# 2_WIZ750SR_Transceiver.net
KiCad netlist of a schematic drawn in Altium Designer
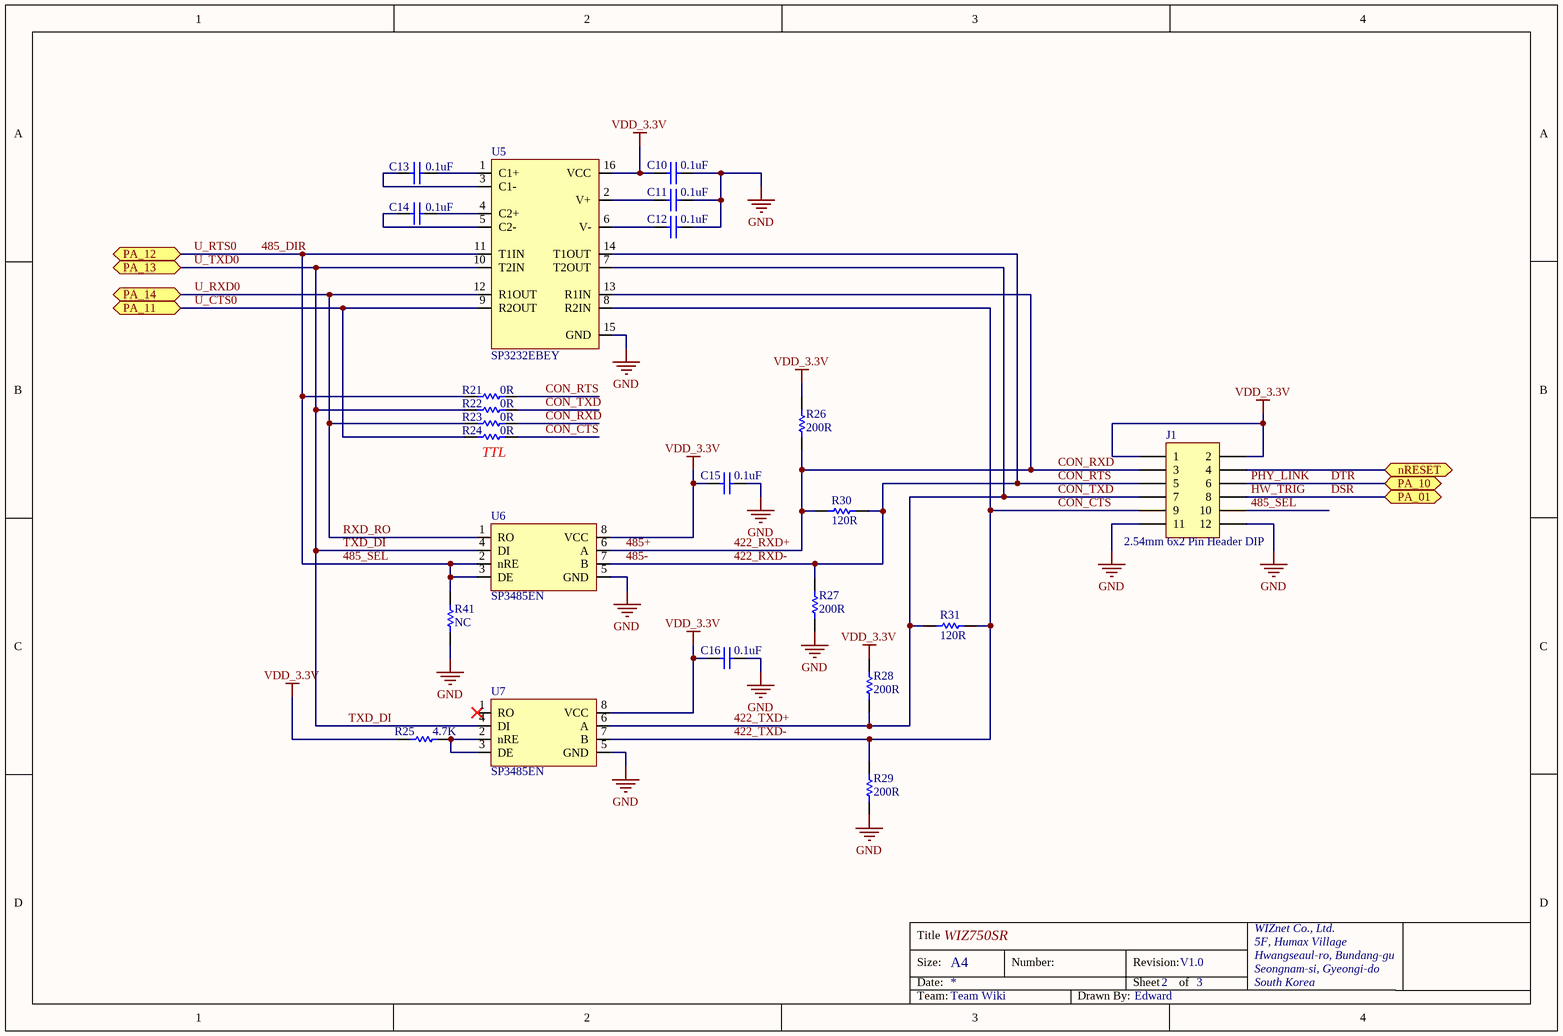
[diagram p0: 2.WIZ750SR_Transceiver.SchDoc]

(export (version "E")
  (design (tool "Eeschema 10.0.6"))
  (components
    (comp (ref "C10")
      (value "0.1uF")
      (footprint "CAP-0402")
      (description "Ceramic CAP 0402(1005)")
      (libsource (lib "Scott_lib") (part "CAP-0402"))
    )
    (comp (ref "C11")
      (value "0.1uF")
      (footprint "CAP-0402")
      (description "Ceramic CAP 0402(1005)")
      (libsource (lib "Scott_lib") (part "CAP-0402"))
    )
    (comp (ref "C12")
      (value "0.1uF")
      (footprint "CAP-0402")
      (description "Ceramic CAP 0402(1005)")
      (libsource (lib "Scott_lib") (part "CAP-0402"))
    )
    (comp (ref "C13")
      (value "0.1uF")
      (footprint "CAP-0402")
      (description "Ceramic CAP 0402(1005)")
      (libsource (lib "Scott_lib") (part "CAP-0402"))
    )
    (comp (ref "C14")
      (value "0.1uF")
      (footprint "CAP-0402")
      (description "Ceramic CAP 0402(1005)")
      (libsource (lib "Scott_lib") (part "CAP-0402"))
    )
    (comp (ref "C15")
      (value "0.1uF")
      (footprint "CAP-0402")
      (description "Ceramic CAP 0402(1005)")
      (libsource (lib "Scott_lib") (part "CAP-0402"))
    )
    (comp (ref "C16")
      (value "0.1uF")
      (footprint "CAP-0402")
      (description "Ceramic CAP 0402(1005)")
      (libsource (lib "Scott_lib") (part "CAP-0402"))
    )
    (comp (ref "J1")
      (value "2.54mm 6x2 Pin Header DIP")
      (footprint "IDC-2X6")
      (description "Header, 6-Pin, Dual row")
      (fields (field (name "PUBLISHER") "Altium Limited"))
      (libsource (lib "Miscellaneous Connectors") (part "Header 6X2"))
    )
    (comp (ref "R21")
      (value "0R")
      (footprint "RES-0402")
      (description "RES-0402")
      (libsource (lib "Scott_lib") (part "RES-0402"))
    )
    (comp (ref "R22")
      (value "0R")
      (footprint "RES-0402")
      (description "RES-0402")
      (libsource (lib "Scott_lib") (part "RES-0402"))
    )
    (comp (ref "R23")
      (value "0R")
      (footprint "RES-0402")
      (description "RES-0402")
      (libsource (lib "Scott_lib") (part "RES-0402"))
    )
    (comp (ref "R24")
      (value "0R")
      (footprint "RES-0402")
      (description "RES-0402")
      (libsource (lib "Scott_lib") (part "RES-0402"))
    )
    (comp (ref "R25")
      (value "4.7K")
      (footprint "RES-0402")
      (description "RES-0402")
      (libsource (lib "Scott_lib") (part "RES-0402"))
    )
    (comp (ref "R26")
      (value "200R")
      (footprint "RES-0402")
      (description "RES-0402")
      (libsource (lib "Scott_lib") (part "RES-0402"))
    )
    (comp (ref "R27")
      (value "200R")
      (footprint "RES-0402")
      (description "RES-0402")
      (libsource (lib "Scott_lib") (part "RES-0402"))
    )
    (comp (ref "R28")
      (value "200R")
      (footprint "RES-0402")
      (description "RES-0402")
      (libsource (lib "Scott_lib") (part "RES-0402"))
    )
    (comp (ref "R29")
      (value "200R")
      (footprint "RES-0402")
      (description "RES-0402")
      (libsource (lib "Scott_lib") (part "RES-0402"))
    )
    (comp (ref "R30")
      (value "120R")
      (footprint "RES-0402")
      (description "RES-0402")
      (libsource (lib "Scott_lib") (part "RES-0402"))
    )
    (comp (ref "R31")
      (value "120R")
      (footprint "RES-0402")
      (description "RES-0402")
      (libsource (lib "Scott_lib") (part "RES-0402"))
    )
    (comp (ref "R41")
      (value "NC")
      (footprint "RES-0402")
      (description "RES-0402")
      (libsource (lib "Scott_lib") (part "RES-0402"))
    )
    (comp (ref "U5")
      (value "SP3232EBEY")
      (footprint "TSSOP16(0.65/6.4)")
      (description "True +3.0V to +5.5V RS-232 Transceivers TSSOP16")
      (libsource (lib "Scott_lib") (part "SP3232EBEY"))
    )
    (comp (ref "U6")
      (value "SP3485EN")
      (footprint "SO-08")
      (description "SP3485EN SOIC8")
      (libsource (lib "SP3485EN") (part "SP3485EN"))
    )
    (comp (ref "U7")
      (value "SP3485EN")
      (footprint "SO-08")
      (description "SP3485EN SOIC8")
      (libsource (lib "SP3485EN") (part "SP3485EN"))
    )
  )
  (nets
    (net (code "1") (name "/422_RXD+") (class "Default")
      (node (ref "J1") (pin "3") (pinfunction "3_3") (pintype "passive"))
      (node (ref "R23") (pin "1") (pinfunction "1_1") (pintype "passive"))
      (node (ref "R26") (pin "2") (pinfunction "2_2") (pintype "passive"))
      (node (ref "R30") (pin "2") (pinfunction "2_2") (pintype "passive"))
      (node (ref "U5") (pin "13") (pinfunction "R1IN_13") (pintype "passive"))
      (node (ref "U6") (pin "6") (pinfunction "A_6") (pintype "passive"))
    )
    (net (code "2") (name "/422_RXD-") (class "Default")
      (node (ref "J1") (pin "5") (pinfunction "5_5") (pintype "passive"))
      (node (ref "R21") (pin "1") (pinfunction "1_1") (pintype "passive"))
      (node (ref "R27") (pin "1") (pinfunction "1_1") (pintype "passive"))
      (node (ref "R30") (pin "1") (pinfunction "1_1") (pintype "passive"))
      (node (ref "U5") (pin "14") (pinfunction "T1OUT_14") (pintype "passive"))
      (node (ref "U6") (pin "7") (pinfunction "B_7") (pintype "passive"))
    )
    (net (code "3") (name "/422_TXD+") (class "Default")
      (node (ref "J1") (pin "7") (pinfunction "7_7") (pintype "passive"))
      (node (ref "R22") (pin "1") (pinfunction "1_1") (pintype "passive"))
      (node (ref "R28") (pin "2") (pinfunction "2_2") (pintype "passive"))
      (node (ref "R31") (pin "2") (pinfunction "2_2") (pintype "passive"))
      (node (ref "U5") (pin "7") (pinfunction "T2OUT_7") (pintype "passive"))
      (node (ref "U7") (pin "6") (pinfunction "A_6") (pintype "passive"))
    )
    (net (code "4") (name "/422_TXD-") (class "Default")
      (node (ref "J1") (pin "9") (pinfunction "9_9") (pintype "passive"))
      (node (ref "R24") (pin "1") (pinfunction "1_1") (pintype "passive"))
      (node (ref "R29") (pin "1") (pinfunction "1_1") (pintype "passive"))
      (node (ref "R31") (pin "1") (pinfunction "1_1") (pintype "passive"))
      (node (ref "U5") (pin "8") (pinfunction "R2IN_8") (pintype "passive"))
      (node (ref "U7") (pin "7") (pinfunction "B_7") (pintype "passive"))
    )
    (net (code "5") (name "/485_DIR") (class "Default")
      (node (ref "J1") (pin "10") (pinfunction "10_10") (pintype "passive"))
      (node (ref "R21") (pin "2") (pinfunction "2_2") (pintype "passive"))
      (node (ref "R41") (pin "1") (pinfunction "1_1") (pintype "passive"))
      (node (ref "U5") (pin "11") (pinfunction "T1IN_11") (pintype "passive"))
      (node (ref "U6") (pin "2") (pinfunction "nRE_2") (pintype "passive"))
      (node (ref "U6") (pin "3") (pinfunction "DE_3") (pintype "passive"))
    )
    (net (code "6") (name "/DSR") (class "Default")
      (node (ref "J1") (pin "8") (pinfunction "8_8") (pintype "passive"))
    )
    (net (code "7") (name "/DTR") (class "Default")
      (node (ref "J1") (pin "6") (pinfunction "6_6") (pintype "passive"))
    )
    (net (code "8") (name "/RXD_RO") (class "Default")
      (node (ref "R23") (pin "2") (pinfunction "2_2") (pintype "passive"))
      (node (ref "U5") (pin "12") (pinfunction "R1OUT_12") (pintype "passive"))
      (node (ref "U6") (pin "1") (pinfunction "RO_1") (pintype "passive"))
    )
    (net (code "9") (name "/TXD_DI") (class "Default")
      (node (ref "R22") (pin "2") (pinfunction "2_2") (pintype "passive"))
      (node (ref "U5") (pin "10") (pinfunction "T2IN_10") (pintype "passive"))
      (node (ref "U6") (pin "4") (pinfunction "DI_4") (pintype "passive"))
      (node (ref "U7") (pin "4") (pinfunction "DI_4") (pintype "passive"))
    )
    (net (code "10") (name "/U_CTS0") (class "Default")
      (node (ref "R24") (pin "2") (pinfunction "2_2") (pintype "passive"))
      (node (ref "U5") (pin "9") (pinfunction "R2OUT_9") (pintype "passive"))
    )
    (net (code "11") (name "/nRESET") (class "Default")
      (node (ref "J1") (pin "4") (pinfunction "4_4") (pintype "passive"))
    )
    (net (code "12") (name "GND") (class "Default")
      (node (ref "C10") (pin "1") (pinfunction "1_1") (pintype "passive"))
      (node (ref "C11") (pin "1") (pinfunction "1_1") (pintype "passive"))
      (node (ref "C12") (pin "1") (pinfunction "1_1") (pintype "passive"))
      (node (ref "C15") (pin "1") (pinfunction "1_1") (pintype "passive"))
      (node (ref "C16") (pin "1") (pinfunction "1_1") (pintype "passive"))
      (node (ref "J1") (pin "11") (pinfunction "11_11") (pintype "passive"))
      (node (ref "J1") (pin "12") (pinfunction "12_12") (pintype "passive"))
      (node (ref "R27") (pin "2") (pinfunction "2_2") (pintype "passive"))
      (node (ref "R29") (pin "2") (pinfunction "2_2") (pintype "passive"))
      (node (ref "R41") (pin "2") (pinfunction "2_2") (pintype "passive"))
      (node (ref "U5") (pin "15") (pinfunction "GND_15") (pintype "passive"))
      (node (ref "U6") (pin "5") (pinfunction "GND_5") (pintype "passive"))
      (node (ref "U7") (pin "5") (pinfunction "GND_5") (pintype "passive"))
    )
    (net (code "13") (name "Net-(U5-C1+)") (class "Default")
      (node (ref "C13") (pin "1") (pinfunction "1_1") (pintype "passive"))
      (node (ref "U5") (pin "1") (pinfunction "C1+_1") (pintype "passive"))
    )
    (net (code "14") (name "Net-(U5-C1-)") (class "Default")
      (node (ref "C13") (pin "2") (pinfunction "2_2") (pintype "passive"))
      (node (ref "U5") (pin "3") (pinfunction "C1-_3") (pintype "passive"))
    )
    (net (code "15") (name "Net-(U5-C2+)") (class "Default")
      (node (ref "C14") (pin "1") (pinfunction "1_1") (pintype "passive"))
      (node (ref "U5") (pin "4") (pinfunction "C2+_4") (pintype "passive"))
    )
    (net (code "16") (name "Net-(U5-C2-)") (class "Default")
      (node (ref "C14") (pin "2") (pinfunction "2_2") (pintype "passive"))
      (node (ref "U5") (pin "5") (pinfunction "C2-_5") (pintype "passive"))
    )
    (net (code "17") (name "Net-(U5-V+)") (class "Default")
      (node (ref "C11") (pin "2") (pinfunction "2_2") (pintype "passive"))
      (node (ref "U5") (pin "2") (pinfunction "V+_2") (pintype "passive"))
    )
    (net (code "18") (name "Net-(U5-V-)") (class "Default")
      (node (ref "C12") (pin "2") (pinfunction "2_2") (pintype "passive"))
      (node (ref "U5") (pin "6") (pinfunction "V-_6") (pintype "passive"))
    )
    (net (code "19") (name "Net-(U7-DE)") (class "Default")
      (node (ref "R25") (pin "1") (pinfunction "1_1") (pintype "passive"))
      (node (ref "U7") (pin "2") (pinfunction "nRE_2") (pintype "passive"))
      (node (ref "U7") (pin "3") (pinfunction "DE_3") (pintype "passive"))
    )
    (net (code "20") (name "VDD_3.3V") (class "Default")
      (node (ref "C10") (pin "2") (pinfunction "2_2") (pintype "passive"))
      (node (ref "C15") (pin "2") (pinfunction "2_2") (pintype "passive"))
      (node (ref "C16") (pin "2") (pinfunction "2_2") (pintype "passive"))
      (node (ref "J1") (pin "1") (pinfunction "1_1") (pintype "passive"))
      (node (ref "J1") (pin "2") (pinfunction "2_2") (pintype "passive"))
      (node (ref "R25") (pin "2") (pinfunction "2_2") (pintype "passive"))
      (node (ref "R26") (pin "1") (pinfunction "1_1") (pintype "passive"))
      (node (ref "R28") (pin "1") (pinfunction "1_1") (pintype "passive"))
      (node (ref "U5") (pin "16") (pinfunction "VCC_16") (pintype "passive"))
      (node (ref "U6") (pin "8") (pinfunction "VCC_8") (pintype "passive"))
      (node (ref "U7") (pin "8") (pinfunction "VCC_8") (pintype "passive"))
    )
    (net (code "21") (name "unconnected-(U7-RO-Pad1)") (class "Default")
      (node (ref "U7") (pin "1") (pinfunction "RO_1") (pintype "passive+no_connect"))
    )
  )
)
